# RS232.net
KiCad netlist of a schematic drawn in Altium Designer
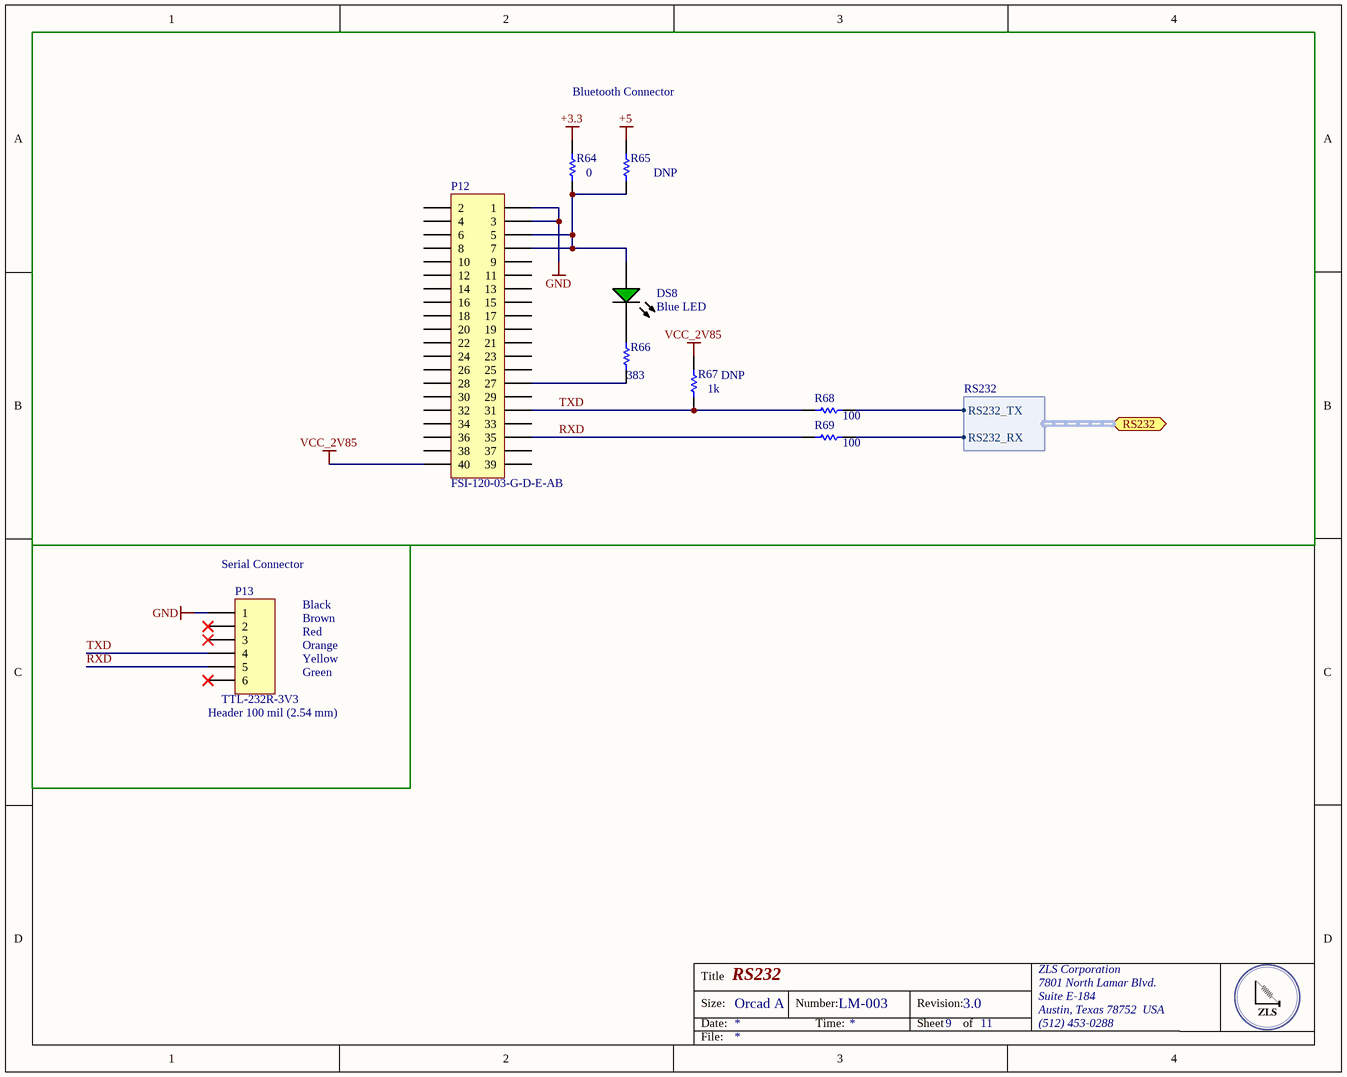
[diagram p0: RS232.SchDoc]

(export (version "E")
  (design (tool "Eeschema 10.0.6"))
  (components
    (comp (ref "DS8")
      (value "Blue LED")
      (footprint "KING-LED0603-25-GREEN_V")
      (description "LED 468NM BLUE CLEAR 0603 SMD")
      (libsource (lib "Altium Content Vault") (part "CMP-0239-00001-1"))
    )
    (comp (ref "P12")
      (value "FSI-120-03-G-D-E-AB")
      (footprint "FSI-120-03-G-D-E-AB")
      (description "1MM SINGLE ELEMENT INTERFACE")
      (libsource (lib "Miscellaneous Connectors") (part "Header 20X2"))
    )
    (comp (ref "P13")
      (value "Header 100 mil (2.54 mm)")
      (footprint "HDR1X6")
      (description "CABLE USB SERIAL 3.3V 2MM HEADER")
      (libsource (lib "Miscellaneous Connectors") (part "Header 6H"))
    )
    (comp (ref "R64")
      (value "RES SMD 0.0 OHM JUMPER 1/8W 0805")
      (footprint "RESC0805(2012)_M")
      (fields
        (field (name "MANUFACTURER") "Vishay")
        (field (name "MANUFACTURER PART NUMBER") "CRCW08050000Z0EA")
        (field (name "RESISTANCE") "0")
        (field (name "TOLERANCE") "1%")
      )
      (libsource (lib "Altium Content Vault") (part "CMP-1013-00017-1"))
    )
    (comp (ref "R65")
      (value "DNP")
      (footprint "RESC0805(2012)_M")
      (description "RES SMD 0.0 OHM JUMPER 1/8W 0805")
      (fields
        (field (name "MANUFACTURER") "Vishay")
        (field (name "MANUFACTURER PART NUMBER") "CRCW08050000Z0EA")
      )
      (libsource (lib "Altium Content Vault") (part "CMP-1013-00017-1"))
    )
    (comp (ref "R66")
      (value "RES SMD 383 OHM 1% 1/8W 0805")
      (footprint "RESC0805(2012)_M")
      (fields
        (field (name "MANUFACTURER") "Vishay Dale")
        (field (name "MANUFACTURER PART NUMBER") "CRCW0805383RFKEA")
        (field (name "RESISTANCE (OHMS)") "383")
        (field (name "TOLERANCE") "±1%")
      )
      (libsource (lib "Altium Content Vault") (part "CMP-1013-00017-1"))
    )
    (comp (ref "R67")
      (value "DNP")
      (footprint "RESC0805(2012)_M")
      (description "RES SMD 1K OHM 1% 1/2W 0805")
      (fields
        (field (name "MANUFACTURER") "Vishay Dale")
        (field (name "MANUFACTURER PART NUMBER") "CRCW08051K00FKEAHP")
        (field (name "RESISTANCE (OHMS)") "1k")
      )
      (libsource (lib "Altium Content Vault") (part "CMP-1013-00017-1"))
    )
    (comp (ref "R68")
      (value "RES SMD 100 OHM 1% 1/8W 0805")
      (footprint "RESC0805(2012)_L")
      (fields
        (field (name "MANUFACTURER") "Vishay Dale")
        (field (name "MANUFACTURER PART NUMBER") "CRCW0805100RFKEA")
        (field (name "RESISTANCE (OHMS)") "100")
        (field (name "TOLERANCE") "±1%")
      )
      (libsource (lib "Altium Content Vault") (part "CMP-1013-00393-1"))
    )
    (comp (ref "R69")
      (value "RES SMD 100 OHM 1% 1/8W 0805")
      (footprint "RESC0805(2012)_N")
      (fields
        (field (name "MANUFACTURER") "Vishay Dale")
        (field (name "MANUFACTURER PART NUMBER") "CRCW0805100RFKEA")
        (field (name "RESISTANCE (OHMS)") "100")
        (field (name "TOLERANCE") "±1%")
      )
      (libsource (lib "Altium Content Vault") (part "CMP-1013-00393-1"))
    )
  )
  (nets
    (net (code "2") (name "+3.3") (class "Default")
      (node (ref "R64") (pin "2") (pinfunction "2_2") (pintype "passive"))
    )
    (net (code "3") (name "+5") (class "Default")
      (node (ref "R65") (pin "2") (pinfunction "2_2") (pintype "passive"))
    )
    (net (code "4") (name "/RS232_RX") (class "Default")
      (node (ref "R69") (pin "1") (pinfunction "1_1") (pintype "passive"))
    )
    (net (code "5") (name "/RS232_TX") (class "Default")
      (node (ref "R68") (pin "1") (pinfunction "1_1") (pintype "passive"))
    )
    (net (code "6") (name "/RXD") (class "Default")
      (node (ref "P12") (pin "35") (pinfunction "35_35") (pintype "passive"))
      (node (ref "P13") (pin "5") (pinfunction "5_5") (pintype "passive"))
      (node (ref "R69") (pin "2") (pinfunction "2_2") (pintype "passive"))
    )
    (net (code "7") (name "/TXD") (class "Default")
      (node (ref "P12") (pin "31") (pinfunction "31_31") (pintype "passive"))
      (node (ref "P13") (pin "4") (pinfunction "4_4") (pintype "passive"))
      (node (ref "R67") (pin "1") (pinfunction "1_1") (pintype "passive"))
      (node (ref "R68") (pin "2") (pinfunction "2_2") (pintype "passive"))
    )
    (net (code "9") (name "GND") (class "Default")
      (node (ref "P12") (pin "1") (pinfunction "1_1") (pintype "passive"))
      (node (ref "P12") (pin "3") (pinfunction "3_3") (pintype "passive"))
      (node (ref "P13") (pin "1") (pinfunction "1_1") (pintype "passive"))
    )
    (net (code "10") (name "Net-(DS8-A)") (class "Default")
      (node (ref "DS8") (pin "1") (pinfunction "A_1") (pintype "passive"))
      (node (ref "P12") (pin "5") (pinfunction "5_5") (pintype "passive"))
      (node (ref "P12") (pin "7") (pinfunction "7_7") (pintype "passive"))
      (node (ref "R64") (pin "1") (pinfunction "1_1") (pintype "passive"))
      (node (ref "R65") (pin "1") (pinfunction "1_1") (pintype "passive"))
    )
    (net (code "11") (name "Net-(DS8-K)") (class "Default")
      (node (ref "DS8") (pin "2") (pinfunction "K_2") (pintype "passive"))
      (node (ref "R66") (pin "2") (pinfunction "2_2") (pintype "passive"))
    )
    (net (code "12") (name "Net-(P12-Pad27)") (class "Default")
      (node (ref "P12") (pin "27") (pinfunction "27_27") (pintype "passive"))
      (node (ref "R66") (pin "1") (pinfunction "1_1") (pintype "passive"))
    )
    (net (code "13") (name "VCC_2V85") (class "Default")
      (node (ref "P12") (pin "40") (pinfunction "40_40") (pintype "passive"))
      (node (ref "R67") (pin "2") (pinfunction "2_2") (pintype "passive"))
    )
    (net (code "14") (name "unconnected-(P12-Pad2)") (class "Default")
      (node (ref "P12") (pin "2") (pinfunction "2_2") (pintype "passive"))
    )
    (net (code "15") (name "unconnected-(P12-Pad4)") (class "Default")
      (node (ref "P12") (pin "4") (pinfunction "4_4") (pintype "passive"))
    )
    (net (code "16") (name "unconnected-(P12-Pad6)") (class "Default")
      (node (ref "P12") (pin "6") (pinfunction "6_6") (pintype "passive"))
    )
    (net (code "17") (name "unconnected-(P12-Pad8)") (class "Default")
      (node (ref "P12") (pin "8") (pinfunction "8_8") (pintype "passive"))
    )
    (net (code "18") (name "unconnected-(P12-Pad9)") (class "Default")
      (node (ref "P12") (pin "9") (pinfunction "9_9") (pintype "passive"))
    )
    (net (code "19") (name "unconnected-(P12-Pad10)") (class "Default")
      (node (ref "P12") (pin "10") (pinfunction "10_10") (pintype "passive"))
    )
    (net (code "20") (name "unconnected-(P12-Pad11)") (class "Default")
      (node (ref "P12") (pin "11") (pinfunction "11_11") (pintype "passive"))
    )
    (net (code "21") (name "unconnected-(P12-Pad12)") (class "Default")
      (node (ref "P12") (pin "12") (pinfunction "12_12") (pintype "passive"))
    )
    (net (code "22") (name "unconnected-(P12-Pad13)") (class "Default")
      (node (ref "P12") (pin "13") (pinfunction "13_13") (pintype "passive"))
    )
    (net (code "23") (name "unconnected-(P12-Pad14)") (class "Default")
      (node (ref "P12") (pin "14") (pinfunction "14_14") (pintype "passive"))
    )
    (net (code "24") (name "unconnected-(P12-Pad15)") (class "Default")
      (node (ref "P12") (pin "15") (pinfunction "15_15") (pintype "passive"))
    )
    (net (code "25") (name "unconnected-(P12-Pad16)") (class "Default")
      (node (ref "P12") (pin "16") (pinfunction "16_16") (pintype "passive"))
    )
    (net (code "26") (name "unconnected-(P12-Pad17)") (class "Default")
      (node (ref "P12") (pin "17") (pinfunction "17_17") (pintype "passive"))
    )
    (net (code "27") (name "unconnected-(P12-Pad18)") (class "Default")
      (node (ref "P12") (pin "18") (pinfunction "18_18") (pintype "passive"))
    )
    (net (code "28") (name "unconnected-(P12-Pad19)") (class "Default")
      (node (ref "P12") (pin "19") (pinfunction "19_19") (pintype "passive"))
    )
    (net (code "29") (name "unconnected-(P12-Pad20)") (class "Default")
      (node (ref "P12") (pin "20") (pinfunction "20_20") (pintype "passive"))
    )
    (net (code "30") (name "unconnected-(P12-Pad21)") (class "Default")
      (node (ref "P12") (pin "21") (pinfunction "21_21") (pintype "passive"))
    )
    (net (code "31") (name "unconnected-(P12-Pad22)") (class "Default")
      (node (ref "P12") (pin "22") (pinfunction "22_22") (pintype "passive"))
    )
    (net (code "32") (name "unconnected-(P12-Pad23)") (class "Default")
      (node (ref "P12") (pin "23") (pinfunction "23_23") (pintype "passive"))
    )
    (net (code "33") (name "unconnected-(P12-Pad24)") (class "Default")
      (node (ref "P12") (pin "24") (pinfunction "24_24") (pintype "passive"))
    )
    (net (code "34") (name "unconnected-(P12-Pad25)") (class "Default")
      (node (ref "P12") (pin "25") (pinfunction "25_25") (pintype "passive"))
    )
    (net (code "35") (name "unconnected-(P12-Pad26)") (class "Default")
      (node (ref "P12") (pin "26") (pinfunction "26_26") (pintype "passive"))
    )
    (net (code "36") (name "unconnected-(P12-Pad28)") (class "Default")
      (node (ref "P12") (pin "28") (pinfunction "28_28") (pintype "passive"))
    )
    (net (code "37") (name "unconnected-(P12-Pad29)") (class "Default")
      (node (ref "P12") (pin "29") (pinfunction "29_29") (pintype "passive"))
    )
    (net (code "38") (name "unconnected-(P12-Pad30)") (class "Default")
      (node (ref "P12") (pin "30") (pinfunction "30_30") (pintype "passive"))
    )
    (net (code "39") (name "unconnected-(P12-Pad32)") (class "Default")
      (node (ref "P12") (pin "32") (pinfunction "32_32") (pintype "passive"))
    )
    (net (code "40") (name "unconnected-(P12-Pad33)") (class "Default")
      (node (ref "P12") (pin "33") (pinfunction "33_33") (pintype "passive"))
    )
    (net (code "41") (name "unconnected-(P12-Pad34)") (class "Default")
      (node (ref "P12") (pin "34") (pinfunction "34_34") (pintype "passive"))
    )
    (net (code "42") (name "unconnected-(P12-Pad36)") (class "Default")
      (node (ref "P12") (pin "36") (pinfunction "36_36") (pintype "passive"))
    )
    (net (code "43") (name "unconnected-(P12-Pad37)") (class "Default")
      (node (ref "P12") (pin "37") (pinfunction "37_37") (pintype "passive"))
    )
    (net (code "44") (name "unconnected-(P12-Pad38)") (class "Default")
      (node (ref "P12") (pin "38") (pinfunction "38_38") (pintype "passive"))
    )
    (net (code "45") (name "unconnected-(P12-Pad39)") (class "Default")
      (node (ref "P12") (pin "39") (pinfunction "39_39") (pintype "passive"))
    )
    (net (code "46") (name "unconnected-(P13-Pad2)") (class "Default")
      (node (ref "P13") (pin "2") (pinfunction "2_2") (pintype "passive+no_connect"))
    )
    (net (code "47") (name "unconnected-(P13-Pad3)") (class "Default")
      (node (ref "P13") (pin "3") (pinfunction "3_3") (pintype "passive+no_connect"))
    )
    (net (code "48") (name "unconnected-(P13-Pad6)") (class "Default")
      (node (ref "P13") (pin "6") (pinfunction "6_6") (pintype "passive+no_connect"))
    )
  )
)
